# Nivel_inferior.net
KiCad netlist of a schematic drawn in EAGLE
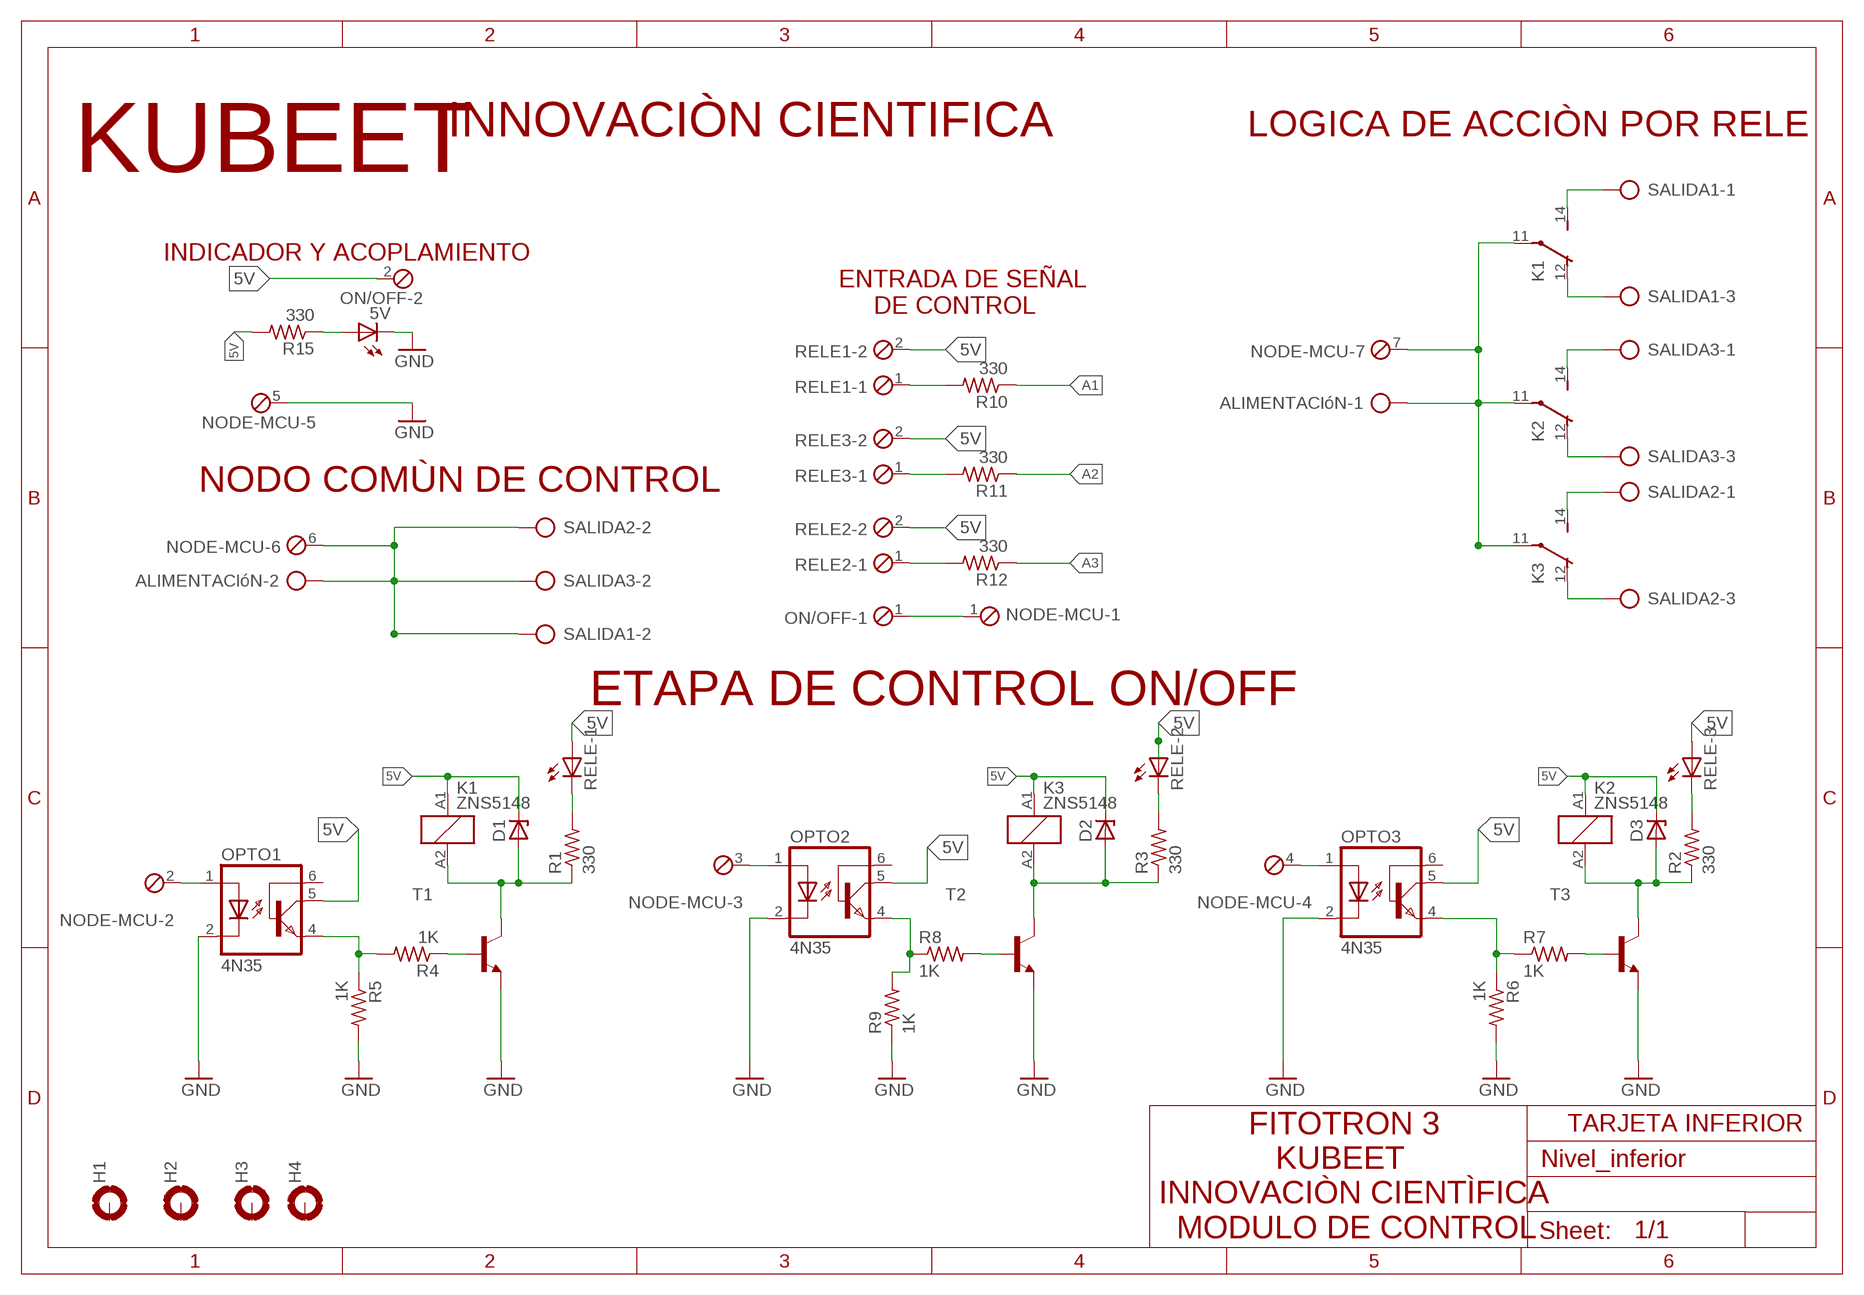
[diagram p0: schematic, sheet 1]

(export (version "E")
  (design (tool "Eeschema 10.0.6"))
  (components
    (comp (ref "5V")
      (value "LED5MM")
      (footprint "eagle-import:LED5MM")
      (libsource (lib "eagle-import") (part "LED5MM"))
    )
    (comp (ref "ALIMENTACIóN")
      (value "AK300/2")
      (footprint "eagle-import:AK300_2")
      (libsource (lib "eagle-import") (part "AK300/2"))
    )
    (comp (ref "D1")
      (value "1N821")
      (footprint "eagle-import:DO35Z10")
      (libsource (lib "eagle-import") (part "1N821"))
    )
    (comp (ref "D2")
      (value "1N821")
      (footprint "eagle-import:DO35Z10")
      (libsource (lib "eagle-import") (part "1N821"))
    )
    (comp (ref "D3")
      (value "1N821")
      (footprint "eagle-import:DO35Z10")
      (libsource (lib "eagle-import") (part "1N821"))
    )
    (comp (ref "H1")
      (value "MOUNT-PAD-ROUND3.6")
      (footprint "eagle-import:3,6-PAD")
      (libsource (lib "eagle-import") (part "MOUNT-PAD-ROUND3.6"))
    )
    (comp (ref "H2")
      (value "MOUNT-PAD-ROUND3.6")
      (footprint "eagle-import:3,6-PAD")
      (libsource (lib "eagle-import") (part "MOUNT-PAD-ROUND3.6"))
    )
    (comp (ref "H3")
      (value "MOUNT-PAD-ROUND3.6")
      (footprint "eagle-import:3,6-PAD")
      (libsource (lib "eagle-import") (part "MOUNT-PAD-ROUND3.6"))
    )
    (comp (ref "H4")
      (value "MOUNT-PAD-ROUND3.6")
      (footprint "eagle-import:3,6-PAD")
      (libsource (lib "eagle-import") (part "MOUNT-PAD-ROUND3.6"))
    )
    (comp (ref "K1")
      (value "ZNS5148")
      (footprint "eagle-import:ZN5")
      (libsource (lib "eagle-import") (part "ZNS5148"))
    )
    (comp (ref "K2")
      (value "ZNS5148")
      (footprint "eagle-import:ZN5")
      (libsource (lib "eagle-import") (part "ZNS5148"))
    )
    (comp (ref "K3")
      (value "ZNS5148")
      (footprint "eagle-import:ZN5")
      (libsource (lib "eagle-import") (part "ZNS5148"))
    )
    (comp (ref "NODE-MCU")
      (value "MPT7")
      (footprint "eagle-import:7POL254")
      (libsource (lib "eagle-import") (part "MPT7"))
    )
    (comp (ref "ON/OFF")
      (value "MPT2")
      (footprint "eagle-import:2POL254")
      (libsource (lib "eagle-import") (part "MPT2"))
    )
    (comp (ref "OPTO1")
      (value "4N35")
      (footprint "eagle-import:DIL06")
      (fields (field (name "MF") "FAIRCHILD SEMICONDUCTOR"))
      (libsource (lib "eagle-import") (part "4N35"))
    )
    (comp (ref "OPTO2")
      (value "4N35")
      (footprint "eagle-import:DIL06")
      (fields (field (name "MF") "FAIRCHILD SEMICONDUCTOR"))
      (libsource (lib "eagle-import") (part "4N35"))
    )
    (comp (ref "OPTO3")
      (value "4N35")
      (footprint "eagle-import:DIL06")
      (fields (field (name "MF") "FAIRCHILD SEMICONDUCTOR"))
      (libsource (lib "eagle-import") (part "4N35"))
    )
    (comp (ref "R1")
      (value "330")
      (footprint "eagle-import:0207_7")
      (libsource (lib "eagle-import") (part "R-US_0207/7"))
    )
    (comp (ref "R2")
      (value "330")
      (footprint "eagle-import:0207_7")
      (libsource (lib "eagle-import") (part "R-US_0207/7"))
    )
    (comp (ref "R3")
      (value "330")
      (footprint "eagle-import:0207_7")
      (libsource (lib "eagle-import") (part "R-US_0207/7"))
    )
    (comp (ref "R4")
      (value "1K")
      (footprint "eagle-import:0207_7")
      (libsource (lib "eagle-import") (part "R-US_0207/7"))
    )
    (comp (ref "R5")
      (value "1K")
      (footprint "eagle-import:0207_7")
      (libsource (lib "eagle-import") (part "R-US_0207/7"))
    )
    (comp (ref "R6")
      (value "1K")
      (footprint "eagle-import:0207_7")
      (libsource (lib "eagle-import") (part "R-US_0207/7"))
    )
    (comp (ref "R7")
      (value "1K")
      (footprint "eagle-import:0207_7")
      (libsource (lib "eagle-import") (part "R-US_0207/7"))
    )
    (comp (ref "R8")
      (value "1K")
      (footprint "eagle-import:0207_7")
      (libsource (lib "eagle-import") (part "R-US_0207/7"))
    )
    (comp (ref "R9")
      (value "1K")
      (footprint "eagle-import:0207_7")
      (libsource (lib "eagle-import") (part "R-US_0207/7"))
    )
    (comp (ref "R10")
      (value "330")
      (footprint "eagle-import:0207_7")
      (libsource (lib "eagle-import") (part "R-US_0207/7"))
    )
    (comp (ref "R11")
      (value "330")
      (footprint "eagle-import:0207_7")
      (libsource (lib "eagle-import") (part "R-US_0207/7"))
    )
    (comp (ref "R12")
      (value "330")
      (footprint "eagle-import:0207_7")
      (libsource (lib "eagle-import") (part "R-US_0207/7"))
    )
    (comp (ref "R15")
      (value "330")
      (footprint "eagle-import:0207_7")
      (libsource (lib "eagle-import") (part "R-US_0207/7"))
    )
    (comp (ref "RELE-1")
      (value "LED5MM")
      (footprint "eagle-import:LED5MM")
      (libsource (lib "eagle-import") (part "LED5MM"))
    )
    (comp (ref "RELE-2")
      (value "LED5MM")
      (footprint "eagle-import:LED5MM")
      (libsource (lib "eagle-import") (part "LED5MM"))
    )
    (comp (ref "RELE-3")
      (value "LED5MM")
      (footprint "eagle-import:LED5MM")
      (libsource (lib "eagle-import") (part "LED5MM"))
    )
    (comp (ref "RELE1")
      (value "MPT2")
      (footprint "eagle-import:2POL254")
      (libsource (lib "eagle-import") (part "MPT2"))
    )
    (comp (ref "RELE2")
      (value "MPT2")
      (footprint "eagle-import:2POL254")
      (libsource (lib "eagle-import") (part "MPT2"))
    )
    (comp (ref "RELE3")
      (value "MPT2")
      (footprint "eagle-import:2POL254")
      (libsource (lib "eagle-import") (part "MPT2"))
    )
    (comp (ref "SALIDA1")
      (value "AK300/3")
      (footprint "eagle-import:AK300_3")
      (libsource (lib "eagle-import") (part "AK300/3"))
    )
    (comp (ref "SALIDA2")
      (value "AK300/3")
      (footprint "eagle-import:AK300_3")
      (libsource (lib "eagle-import") (part "AK300/3"))
    )
    (comp (ref "SALIDA3")
      (value "AK300/3")
      (footprint "eagle-import:AK300_3")
      (libsource (lib "eagle-import") (part "AK300/3"))
    )
    (comp (ref "T1")
      (value "2N2222-NPN-TO92-EBC")
      (footprint "eagle-import:TO92-EBC")
      (libsource (lib "eagle-import") (part "-NPN-TO92-EBC2N2222"))
    )
    (comp (ref "T2")
      (value "2N2222-NPN-TO92-EBC")
      (footprint "eagle-import:TO92-EBC")
      (libsource (lib "eagle-import") (part "-NPN-TO92-EBC2N2222"))
    )
    (comp (ref "T3")
      (value "2N2222-NPN-TO92-EBC")
      (footprint "eagle-import:TO92-EBC")
      (libsource (lib "eagle-import") (part "-NPN-TO92-EBC2N2222"))
    )
  )
  (nets
    (net (code "1") (name "5V") (class "Default")
      (node (ref "D1") (pin "C") (pinfunction "C_C") (pintype "passive"))
      (node (ref "D2") (pin "C") (pinfunction "C_C") (pintype "passive"))
      (node (ref "D3") (pin "C") (pinfunction "C_C") (pintype "passive"))
      (node (ref "K1") (pin "A1") (pinfunction "1_A1") (pintype "passive"))
      (node (ref "K2") (pin "A1") (pinfunction "1_A1") (pintype "passive"))
      (node (ref "K3") (pin "A1") (pinfunction "1_A1") (pintype "passive"))
      (node (ref "ON/OFF") (pin "2") (pinfunction "1_2") (pintype "passive"))
      (node (ref "OPTO1") (pin "5") (pinfunction "COL_5") (pintype "passive"))
      (node (ref "OPTO2") (pin "5") (pinfunction "COL_5") (pintype "passive"))
      (node (ref "OPTO3") (pin "5") (pinfunction "COL_5") (pintype "passive"))
      (node (ref "R15") (pin "2") (pinfunction "2_2") (pintype "passive"))
      (node (ref "RELE-1") (pin "A") (pinfunction "A_A") (pintype "passive"))
      (node (ref "RELE-2") (pin "A") (pinfunction "A_A") (pintype "passive"))
      (node (ref "RELE-3") (pin "A") (pinfunction "A_A") (pintype "passive"))
      (node (ref "RELE1") (pin "2") (pinfunction "1_2") (pintype "passive"))
      (node (ref "RELE2") (pin "2") (pinfunction "1_2") (pintype "passive"))
      (node (ref "RELE3") (pin "2") (pinfunction "1_2") (pintype "passive"))
    )
    (net (code "2") (name "A1") (class "Default")
      (node (ref "NODE-MCU") (pin "2") (pinfunction "1_2") (pintype "passive"))
      (node (ref "OPTO1") (pin "1") (pinfunction "A_1") (pintype "passive"))
      (node (ref "R10") (pin "1") (pinfunction "1_1") (pintype "passive"))
    )
    (net (code "3") (name "A2") (class "Default")
      (node (ref "NODE-MCU") (pin "4") (pinfunction "1_4") (pintype "passive"))
      (node (ref "OPTO3") (pin "1") (pinfunction "A_1") (pintype "passive"))
      (node (ref "R11") (pin "1") (pinfunction "1_1") (pintype "passive"))
    )
    (net (code "4") (name "A3") (class "Default")
      (node (ref "NODE-MCU") (pin "3") (pinfunction "1_3") (pintype "passive"))
      (node (ref "OPTO2") (pin "1") (pinfunction "A_1") (pintype "passive"))
      (node (ref "R12") (pin "1") (pinfunction "1_1") (pintype "passive"))
    )
    (net (code "5") (name "GND") (class "Default")
      (node (ref "5V") (pin "K") (pinfunction "C_K") (pintype "passive"))
      (node (ref "NODE-MCU") (pin "5") (pinfunction "1_5") (pintype "passive"))
      (node (ref "OPTO1") (pin "2") (pinfunction "C_2") (pintype "passive"))
      (node (ref "OPTO2") (pin "2") (pinfunction "C_2") (pintype "passive"))
      (node (ref "OPTO3") (pin "2") (pinfunction "C_2") (pintype "passive"))
      (node (ref "R5") (pin "2") (pinfunction "2_2") (pintype "passive"))
      (node (ref "R6") (pin "2") (pinfunction "2_2") (pintype "passive"))
      (node (ref "R9") (pin "1") (pinfunction "1_1") (pintype "passive"))
      (node (ref "T1") (pin "E") (pinfunction "E_E") (pintype "passive"))
      (node (ref "T2") (pin "E") (pinfunction "E_E") (pintype "passive"))
      (node (ref "T3") (pin "E") (pinfunction "E_E") (pintype "passive"))
    )
    (net (code "6") (name "Net-(5V-PadA)") (class "Default")
      (node (ref "5V") (pin "A") (pinfunction "A_A") (pintype "passive"))
      (node (ref "R15") (pin "1") (pinfunction "1_1") (pintype "passive"))
    )
    (net (code "7") (name "Net-(ALIMENTACIóNA-KL)") (class "Default")
      (node (ref "ALIMENTACIóN") (pin "1") (pinfunction "KL_1") (pintype "passive"))
      (node (ref "K1") (pin "11") (pinfunction "P_11") (pintype "passive"))
      (node (ref "K2") (pin "11") (pinfunction "P_11") (pintype "passive"))
      (node (ref "K3") (pin "11") (pinfunction "P_11") (pintype "passive"))
      (node (ref "NODE-MCU") (pin "7") (pinfunction "1_7") (pintype "passive"))
    )
    (net (code "8") (name "Net-(ALIMENTACIóNB-KL)") (class "Default")
      (node (ref "ALIMENTACIóN") (pin "2") (pinfunction "KL_2") (pintype "passive"))
      (node (ref "NODE-MCU") (pin "6") (pinfunction "1_6") (pintype "passive"))
      (node (ref "SALIDA1") (pin "2") (pinfunction "KL_2") (pintype "passive"))
      (node (ref "SALIDA2") (pin "2") (pinfunction "KL_2") (pintype "passive"))
      (node (ref "SALIDA3") (pin "2") (pinfunction "KL_2") (pintype "passive"))
    )
    (net (code "9") (name "Net-(K1A-2)") (class "Default")
      (node (ref "D1") (pin "A") (pinfunction "A_A") (pintype "passive"))
      (node (ref "K1") (pin "A2") (pinfunction "2_A2") (pintype "passive"))
      (node (ref "R1") (pin "1") (pinfunction "1_1") (pintype "passive"))
      (node (ref "T1") (pin "C") (pinfunction "C_C") (pintype "passive"))
    )
    (net (code "10") (name "Net-(K1B-O)") (class "Default")
      (node (ref "K1") (pin "12") (pinfunction "O_12") (pintype "passive"))
      (node (ref "SALIDA1") (pin "3") (pinfunction "KL_3") (pintype "passive"))
    )
    (net (code "11") (name "Net-(K1B-S)") (class "Default")
      (node (ref "K1") (pin "14") (pinfunction "S_14") (pintype "passive"))
      (node (ref "SALIDA1") (pin "1") (pinfunction "KL_1") (pintype "passive"))
    )
    (net (code "12") (name "Net-(K2A-2)") (class "Default")
      (node (ref "D3") (pin "A") (pinfunction "A_A") (pintype "passive"))
      (node (ref "K2") (pin "A2") (pinfunction "2_A2") (pintype "passive"))
      (node (ref "R2") (pin "1") (pinfunction "1_1") (pintype "passive"))
      (node (ref "T3") (pin "C") (pinfunction "C_C") (pintype "passive"))
    )
    (net (code "13") (name "Net-(K2B-O)") (class "Default")
      (node (ref "K2") (pin "12") (pinfunction "O_12") (pintype "passive"))
      (node (ref "SALIDA3") (pin "3") (pinfunction "KL_3") (pintype "passive"))
    )
    (net (code "14") (name "Net-(K2B-S)") (class "Default")
      (node (ref "K2") (pin "14") (pinfunction "S_14") (pintype "passive"))
      (node (ref "SALIDA3") (pin "1") (pinfunction "KL_1") (pintype "passive"))
    )
    (net (code "15") (name "Net-(K3A-2)") (class "Default")
      (node (ref "D2") (pin "A") (pinfunction "A_A") (pintype "passive"))
      (node (ref "K3") (pin "A2") (pinfunction "2_A2") (pintype "passive"))
      (node (ref "R3") (pin "1") (pinfunction "1_1") (pintype "passive"))
      (node (ref "T2") (pin "C") (pinfunction "C_C") (pintype "passive"))
    )
    (net (code "16") (name "Net-(K3B-O)") (class "Default")
      (node (ref "K3") (pin "12") (pinfunction "O_12") (pintype "passive"))
      (node (ref "SALIDA2") (pin "3") (pinfunction "KL_3") (pintype "passive"))
    )
    (net (code "17") (name "Net-(K3B-S)") (class "Default")
      (node (ref "K3") (pin "14") (pinfunction "S_14") (pintype "passive"))
      (node (ref "SALIDA2") (pin "1") (pinfunction "KL_1") (pintype "passive"))
    )
    (net (code "18") (name "Net-(NODE-MCU-Pad1)") (class "Default")
      (node (ref "NODE-MCU") (pin "1") (pinfunction "1_1") (pintype "passive"))
      (node (ref "ON/OFF") (pin "1") (pinfunction "1_1") (pintype "passive"))
    )
    (net (code "19") (name "Net-(OPTO1-EMI)") (class "Default")
      (node (ref "OPTO1") (pin "4") (pinfunction "EMI_4") (pintype "passive"))
      (node (ref "R4") (pin "2") (pinfunction "2_2") (pintype "passive"))
      (node (ref "R5") (pin "1") (pinfunction "1_1") (pintype "passive"))
    )
    (net (code "20") (name "Net-(OPTO2-EMI)") (class "Default")
      (node (ref "OPTO2") (pin "4") (pinfunction "EMI_4") (pintype "passive"))
      (node (ref "R8") (pin "1") (pinfunction "1_1") (pintype "passive"))
      (node (ref "R9") (pin "2") (pinfunction "2_2") (pintype "passive"))
    )
    (net (code "21") (name "Net-(OPTO3-EMI)") (class "Default")
      (node (ref "OPTO3") (pin "4") (pinfunction "EMI_4") (pintype "passive"))
      (node (ref "R6") (pin "1") (pinfunction "1_1") (pintype "passive"))
      (node (ref "R7") (pin "1") (pinfunction "1_1") (pintype "passive"))
    )
    (net (code "22") (name "Net-(R4-Pad1)") (class "Default")
      (node (ref "R4") (pin "1") (pinfunction "1_1") (pintype "passive"))
      (node (ref "T1") (pin "B") (pinfunction "B_B") (pintype "passive"))
    )
    (net (code "23") (name "Net-(R7-Pad2)") (class "Default")
      (node (ref "R7") (pin "2") (pinfunction "2_2") (pintype "passive"))
      (node (ref "T3") (pin "B") (pinfunction "B_B") (pintype "passive"))
    )
    (net (code "24") (name "Net-(R8-Pad2)") (class "Default")
      (node (ref "R8") (pin "2") (pinfunction "2_2") (pintype "passive"))
      (node (ref "T2") (pin "B") (pinfunction "B_B") (pintype "passive"))
    )
    (net (code "25") (name "Net-(R10-Pad2)") (class "Default")
      (node (ref "R10") (pin "2") (pinfunction "2_2") (pintype "passive"))
      (node (ref "RELE1") (pin "1") (pinfunction "1_1") (pintype "passive"))
    )
    (net (code "26") (name "Net-(R11-Pad2)") (class "Default")
      (node (ref "R11") (pin "2") (pinfunction "2_2") (pintype "passive"))
      (node (ref "RELE3") (pin "1") (pinfunction "1_1") (pintype "passive"))
    )
    (net (code "27") (name "Net-(R12-Pad2)") (class "Default")
      (node (ref "R12") (pin "2") (pinfunction "2_2") (pintype "passive"))
      (node (ref "RELE2") (pin "1") (pinfunction "1_1") (pintype "passive"))
    )
    (net (code "28") (name "Net-(RELE-1-C)") (class "Default")
      (node (ref "R1") (pin "2") (pinfunction "2_2") (pintype "passive"))
      (node (ref "RELE-1") (pin "K") (pinfunction "C_K") (pintype "passive"))
    )
    (net (code "29") (name "Net-(RELE-2-C)") (class "Default")
      (node (ref "R3") (pin "2") (pinfunction "2_2") (pintype "passive"))
      (node (ref "RELE-2") (pin "K") (pinfunction "C_K") (pintype "passive"))
    )
    (net (code "30") (name "Net-(RELE-3-C)") (class "Default")
      (node (ref "R2") (pin "2") (pinfunction "2_2") (pintype "passive"))
      (node (ref "RELE-3") (pin "K") (pinfunction "C_K") (pintype "passive"))
    )
    (net (code "31") (name "unconnected-(H1-MOUNT-PadB3,6)") (class "Default")
      (node (ref "H1") (pin "B3,6") (pinfunction "MOUNT_B3,6") (pintype "passive"))
    )
    (net (code "32") (name "unconnected-(H2-MOUNT-PadB3,6)") (class "Default")
      (node (ref "H2") (pin "B3,6") (pinfunction "MOUNT_B3,6") (pintype "passive"))
    )
    (net (code "33") (name "unconnected-(H3-MOUNT-PadB3,6)") (class "Default")
      (node (ref "H3") (pin "B3,6") (pinfunction "MOUNT_B3,6") (pintype "passive"))
    )
    (net (code "34") (name "unconnected-(H4-MOUNT-PadB3,6)") (class "Default")
      (node (ref "H4") (pin "B3,6") (pinfunction "MOUNT_B3,6") (pintype "passive"))
    )
    (net (code "35") (name "unconnected-(OPTO1-BAS-Pad6)") (class "Default")
      (node (ref "OPTO1") (pin "6") (pinfunction "BAS_6") (pintype "passive"))
    )
    (net (code "36") (name "unconnected-(OPTO2-BAS-Pad6)") (class "Default")
      (node (ref "OPTO2") (pin "6") (pinfunction "BAS_6") (pintype "passive"))
    )
    (net (code "37") (name "unconnected-(OPTO3-BAS-Pad6)") (class "Default")
      (node (ref "OPTO3") (pin "6") (pinfunction "BAS_6") (pintype "passive"))
    )
  )
)
